# alphanewt_v1_0.net
KiCad netlist of a schematic drawn in EAGLE
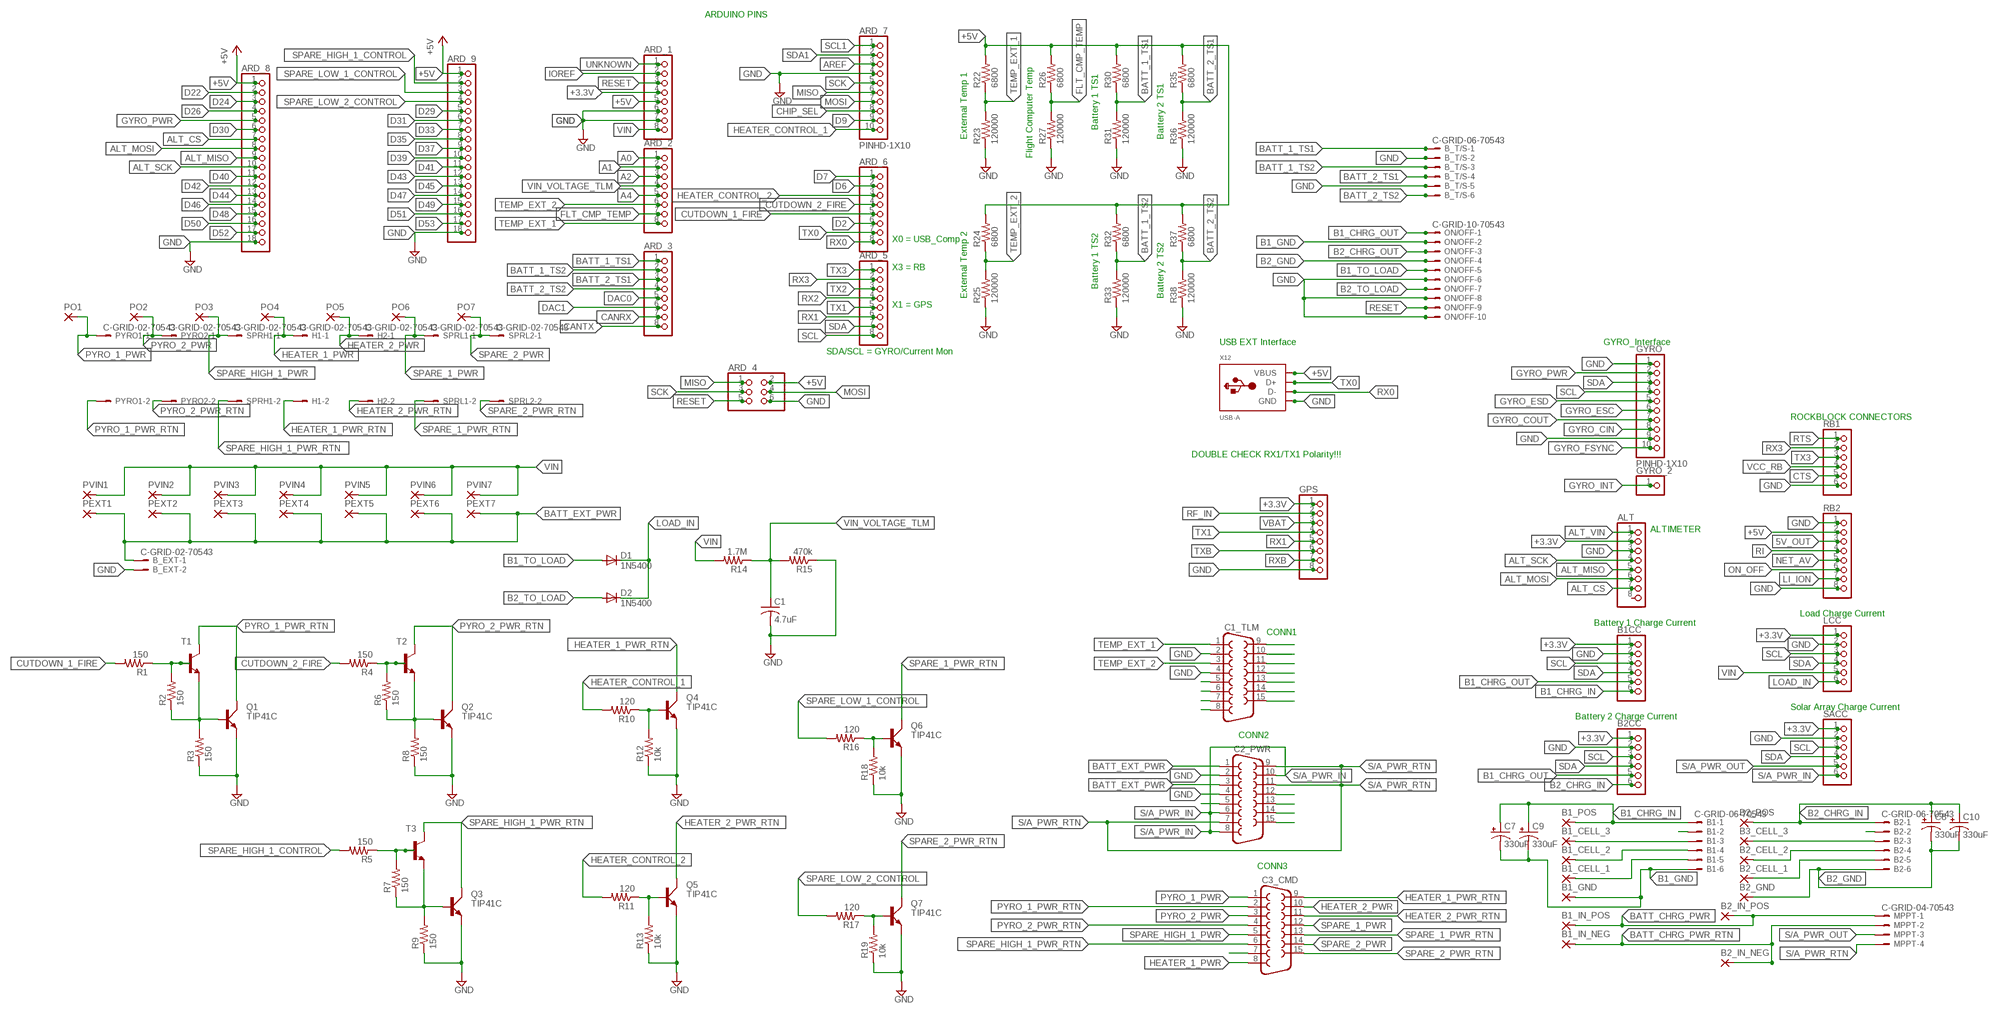
[diagram p0: schematic, sheet 1]

(export (version "E")
  (design (tool "Eeschema 10.0.6"))
  (components
    (comp (ref "ALT")
      (value "PINHD-1X8BIG")
      (footprint "eagle-import:1X08-BIG")
      (libsource (lib "eagle-import") (part "PINHD-1X8BIG"))
    )
    (comp (ref "ARD_1")
      (value "PINHD-1X8BIG")
      (footprint "eagle-import:1X08-BIG")
      (libsource (lib "eagle-import") (part "PINHD-1X8BIG"))
    )
    (comp (ref "ARD_2")
      (value "PINHD-1X8BIG")
      (footprint "eagle-import:1X08-BIG")
      (libsource (lib "eagle-import") (part "PINHD-1X8BIG"))
    )
    (comp (ref "ARD_3")
      (value "PINHD-1X8BIG")
      (footprint "eagle-import:1X08-BIG")
      (libsource (lib "eagle-import") (part "PINHD-1X8BIG"))
    )
    (comp (ref "ARD_4")
      (value "PINHD-2X3")
      (footprint "eagle-import:2X03")
      (libsource (lib "eagle-import") (part "PINHD-2X3"))
    )
    (comp (ref "ARD_5")
      (value "PINHD-1X8BIG")
      (footprint "eagle-import:1X08-BIG")
      (libsource (lib "eagle-import") (part "PINHD-1X8BIG"))
    )
    (comp (ref "ARD_6")
      (value "PINHD-1X8BIG")
      (footprint "eagle-import:1X08-BIG")
      (libsource (lib "eagle-import") (part "PINHD-1X8BIG"))
    )
    (comp (ref "ARD_7")
      (value "PINHD-1X10")
      (footprint "eagle-import:1X10-BIG")
      (libsource (lib "eagle-import") (part "PINHD-1X10"))
    )
    (comp (ref "ARD_8")
      (value "PINHD-1X18-BIG")
      (footprint "eagle-import:1X18-BIG")
      (libsource (lib "eagle-import") (part "PINHD-1X18-BIG"))
    )
    (comp (ref "ARD_9")
      (value "PINHD-1X18-BIG")
      (footprint "eagle-import:1X18-BIG")
      (libsource (lib "eagle-import") (part "PINHD-1X18-BIG"))
    )
    (comp (ref "B1")
      (value "C-GRID-06-70543")
      (footprint "eagle-import:70543-06")
      (fields
        (field (name "MF") "MOLEX")
        (field (name "MPN") "70543-0005")
        (field (name "OC_NEWARK") "59H2647")
      )
      (libsource (lib "eagle-import") (part "C-GRID-06-70543"))
    )
    (comp (ref "B1CC")
      (value "PINHD-1X6B")
      (footprint "eagle-import:1X06-BIG")
      (libsource (lib "eagle-import") (part "PINHD-1X6B"))
    )
    (comp (ref "B1_CELL_1")
      (value "SMD5")
      (footprint "eagle-import:SMD2,54-5,08")
      (libsource (lib "eagle-import") (part "SMD5"))
    )
    (comp (ref "B1_CELL_2")
      (value "SMD5")
      (footprint "eagle-import:SMD2,54-5,08")
      (libsource (lib "eagle-import") (part "SMD5"))
    )
    (comp (ref "B1_CELL_3")
      (value "SMD5")
      (footprint "eagle-import:SMD2,54-5,08")
      (libsource (lib "eagle-import") (part "SMD5"))
    )
    (comp (ref "B1_GND")
      (value "SMD5")
      (footprint "eagle-import:SMD2,54-5,08")
      (libsource (lib "eagle-import") (part "SMD5"))
    )
    (comp (ref "B1_IN_NEG")
      (value "SMD5")
      (footprint "eagle-import:SMD2,54-5,08")
      (libsource (lib "eagle-import") (part "SMD5"))
    )
    (comp (ref "B1_IN_POS")
      (value "SMD5")
      (footprint "eagle-import:SMD2,54-5,08")
      (libsource (lib "eagle-import") (part "SMD5"))
    )
    (comp (ref "B1_POS")
      (value "SMD5")
      (footprint "eagle-import:SMD2,54-5,08")
      (libsource (lib "eagle-import") (part "SMD5"))
    )
    (comp (ref "B2")
      (value "C-GRID-06-70543")
      (footprint "eagle-import:70543-06")
      (fields
        (field (name "MF") "MOLEX")
        (field (name "MPN") "70543-0005")
        (field (name "OC_NEWARK") "59H2647")
      )
      (libsource (lib "eagle-import") (part "C-GRID-06-70543"))
    )
    (comp (ref "B2CC")
      (value "PINHD-1X6B")
      (footprint "eagle-import:1X06-BIG")
      (libsource (lib "eagle-import") (part "PINHD-1X6B"))
    )
    (comp (ref "B2_CELL_1")
      (value "SMD5")
      (footprint "eagle-import:SMD2,54-5,08")
      (libsource (lib "eagle-import") (part "SMD5"))
    )
    (comp (ref "B2_CELL_2")
      (value "SMD5")
      (footprint "eagle-import:SMD2,54-5,08")
      (libsource (lib "eagle-import") (part "SMD5"))
    )
    (comp (ref "B2_GND")
      (value "SMD5")
      (footprint "eagle-import:SMD2,54-5,08")
      (libsource (lib "eagle-import") (part "SMD5"))
    )
    (comp (ref "B2_IN_NEG")
      (value "SMD5")
      (footprint "eagle-import:SMD2,54-5,08")
      (libsource (lib "eagle-import") (part "SMD5"))
    )
    (comp (ref "B2_IN_POS")
      (value "SMD5")
      (footprint "eagle-import:SMD2,54-5,08")
      (libsource (lib "eagle-import") (part "SMD5"))
    )
    (comp (ref "B2_POS")
      (value "SMD5")
      (footprint "eagle-import:SMD2,54-5,08")
      (libsource (lib "eagle-import") (part "SMD5"))
    )
    (comp (ref "B3_CELL_3")
      (value "SMD5")
      (footprint "eagle-import:SMD2,54-5,08")
      (libsource (lib "eagle-import") (part "SMD5"))
    )
    (comp (ref "B_EXT")
      (value "C-GRID-02-70543")
      (footprint "eagle-import:70543-02")
      (fields
        (field (name "MF") "MOLEX")
        (field (name "MPN") "70543-0001")
        (field (name "OC_NEWARK") "59H2645")
      )
      (libsource (lib "eagle-import") (part "C-GRID-02-70543"))
    )
    (comp (ref "B_T/S")
      (value "C-GRID-06-70543")
      (footprint "eagle-import:70543-06")
      (fields
        (field (name "MF") "MOLEX")
        (field (name "MPN") "70543-0005")
        (field (name "OC_NEWARK") "59H2647")
      )
      (libsource (lib "eagle-import") (part "C-GRID-06-70543"))
    )
    (comp (ref "C1")
      (value "4.7uF")
      (footprint "eagle-import:C0805K")
      (fields (field (name "MPN") "C2012X6S1H475K125AC"))
      (libsource (lib "eagle-import") (part "C-USC0805K"))
    )
    (comp (ref "C1_TLM")
      (value "F15HP")
      (footprint "eagle-import:F15HP")
      (fields (field (name "MPN") "5504F1-15S-02A-03"))
      (libsource (lib "eagle-import") (part "F15HP"))
    )
    (comp (ref "C2_PWR")
      (value "F15HP")
      (footprint "eagle-import:F15HP")
      (fields (field (name "MPN") "5504F1-15S-02A-03"))
      (libsource (lib "eagle-import") (part "F15HP"))
    )
    (comp (ref "C3_CMD")
      (value "F15HP")
      (footprint "eagle-import:F15HP")
      (fields (field (name "MPN") "5504F1-15S-02A-03"))
      (libsource (lib "eagle-import") (part "F15HP"))
    )
    (comp (ref "C7")
      (value "330uF")
      (footprint "eagle-import:CT7343")
      (fields (field (name "MPN") "TCN4337M020R0100"))
      (libsource (lib "eagle-import") (part "CPOL-USCT7343"))
    )
    (comp (ref "C8")
      (value "330uF")
      (footprint "eagle-import:CT7343")
      (fields (field (name "MPN") "TCN4337M020R0100"))
      (libsource (lib "eagle-import") (part "CPOL-USCT7343"))
    )
    (comp (ref "C9")
      (value "330uF")
      (footprint "eagle-import:CT7343")
      (fields (field (name "MPN") "TCN4337M020R0100"))
      (libsource (lib "eagle-import") (part "CPOL-USCT7343"))
    )
    (comp (ref "C10")
      (value "330uF")
      (footprint "eagle-import:CT7343")
      (fields (field (name "MPN") "TCN4337M020R0100"))
      (libsource (lib "eagle-import") (part "CPOL-USCT7343"))
    )
    (comp (ref "D1")
      (value "1N5400")
      (footprint "eagle-import:DO201-15")
      (fields (field (name "MPN") "1N5400-E3/54"))
      (libsource (lib "eagle-import") (part "1N5400"))
    )
    (comp (ref "D2")
      (value "1N5400")
      (footprint "eagle-import:DO201-15")
      (fields (field (name "MPN") "1N5400-E3/54"))
      (libsource (lib "eagle-import") (part "1N5400"))
    )
    (comp (ref "GPS")
      (value "PINHD-1X8BIG")
      (footprint "eagle-import:1X08-BIG")
      (libsource (lib "eagle-import") (part "PINHD-1X8BIG"))
    )
    (comp (ref "GYRO")
      (value "PINHD-1X10")
      (footprint "eagle-import:1X10-BIG")
      (libsource (lib "eagle-import") (part "PINHD-1X10"))
    )
    (comp (ref "GYRO_2")
      (value "PINHD-1X1")
      (footprint "eagle-import:1X01")
      (libsource (lib "eagle-import") (part "PINHD-1X1"))
    )
    (comp (ref "H1")
      (value "C-GRID-02-70543")
      (footprint "eagle-import:70543-02")
      (fields
        (field (name "MF") "MOLEX")
        (field (name "MPN") "70543-0001")
        (field (name "OC_NEWARK") "59H2645")
      )
      (libsource (lib "eagle-import") (part "C-GRID-02-70543"))
    )
    (comp (ref "H2")
      (value "C-GRID-02-70543")
      (footprint "eagle-import:70543-02")
      (fields
        (field (name "MF") "MOLEX")
        (field (name "MPN") "70543-0001")
        (field (name "OC_NEWARK") "59H2645")
      )
      (libsource (lib "eagle-import") (part "C-GRID-02-70543"))
    )
    (comp (ref "LCC")
      (value "PINHD-1X6B")
      (footprint "eagle-import:1X06-BIG")
      (libsource (lib "eagle-import") (part "PINHD-1X6B"))
    )
    (comp (ref "MPPT")
      (value "C-GRID-04-70543")
      (footprint "eagle-import:70543-04")
      (fields
        (field (name "MF") "MOLEX")
        (field (name "MPN") "70543-0038")
        (field (name "OC_NEWARK") "59H2665")
      )
      (libsource (lib "eagle-import") (part "C-GRID-04-70543"))
    )
    (comp (ref "ON/OFF")
      (value "C-GRID-10-70543")
      (footprint "eagle-import:70543-10")
      (fields
        (field (name "MF") "MOLEX")
        (field (name "MPN") "70543-0009")
        (field (name "OC_NEWARK") "59H2651")
      )
      (libsource (lib "eagle-import") (part "C-GRID-10-70543"))
    )
    (comp (ref "PEXT1")
      (value "SMD2")
      (footprint "eagle-import:SMD1,27-2,54")
      (libsource (lib "eagle-import") (part "SMD2"))
    )
    (comp (ref "PEXT2")
      (value "SMD2")
      (footprint "eagle-import:SMD1,27-2,54")
      (libsource (lib "eagle-import") (part "SMD2"))
    )
    (comp (ref "PEXT3")
      (value "SMD2")
      (footprint "eagle-import:SMD1,27-2,54")
      (libsource (lib "eagle-import") (part "SMD2"))
    )
    (comp (ref "PEXT4")
      (value "SMD2")
      (footprint "eagle-import:SMD1,27-2,54")
      (libsource (lib "eagle-import") (part "SMD2"))
    )
    (comp (ref "PEXT5")
      (value "SMD2")
      (footprint "eagle-import:SMD1,27-2,54")
      (libsource (lib "eagle-import") (part "SMD2"))
    )
    (comp (ref "PEXT6")
      (value "SMD2")
      (footprint "eagle-import:SMD1,27-2,54")
      (libsource (lib "eagle-import") (part "SMD2"))
    )
    (comp (ref "PEXT7")
      (value "SMD2")
      (footprint "eagle-import:SMD1,27-2,54")
      (libsource (lib "eagle-import") (part "SMD2"))
    )
    (comp (ref "PO1")
      (value "SMD2")
      (footprint "eagle-import:SMD1,27-2,54")
      (libsource (lib "eagle-import") (part "SMD2"))
    )
    (comp (ref "PO2")
      (value "SMD2")
      (footprint "eagle-import:SMD1,27-2,54")
      (libsource (lib "eagle-import") (part "SMD2"))
    )
    (comp (ref "PO3")
      (value "SMD2")
      (footprint "eagle-import:SMD1,27-2,54")
      (libsource (lib "eagle-import") (part "SMD2"))
    )
    (comp (ref "PO4")
      (value "SMD2")
      (footprint "eagle-import:SMD1,27-2,54")
      (libsource (lib "eagle-import") (part "SMD2"))
    )
    (comp (ref "PO5")
      (value "SMD2")
      (footprint "eagle-import:SMD1,27-2,54")
      (libsource (lib "eagle-import") (part "SMD2"))
    )
    (comp (ref "PO6")
      (value "SMD2")
      (footprint "eagle-import:SMD1,27-2,54")
      (libsource (lib "eagle-import") (part "SMD2"))
    )
    (comp (ref "PO7")
      (value "SMD2")
      (footprint "eagle-import:SMD1,27-2,54")
      (libsource (lib "eagle-import") (part "SMD2"))
    )
    (comp (ref "PVIN1")
      (value "SMD2")
      (footprint "eagle-import:SMD1,27-2,54")
      (libsource (lib "eagle-import") (part "SMD2"))
    )
    (comp (ref "PVIN2")
      (value "SMD2")
      (footprint "eagle-import:SMD1,27-2,54")
      (libsource (lib "eagle-import") (part "SMD2"))
    )
    (comp (ref "PVIN3")
      (value "SMD2")
      (footprint "eagle-import:SMD1,27-2,54")
      (libsource (lib "eagle-import") (part "SMD2"))
    )
    (comp (ref "PVIN4")
      (value "SMD2")
      (footprint "eagle-import:SMD1,27-2,54")
      (libsource (lib "eagle-import") (part "SMD2"))
    )
    (comp (ref "PVIN5")
      (value "SMD2")
      (footprint "eagle-import:SMD1,27-2,54")
      (libsource (lib "eagle-import") (part "SMD2"))
    )
    (comp (ref "PVIN6")
      (value "SMD2")
      (footprint "eagle-import:SMD1,27-2,54")
      (libsource (lib "eagle-import") (part "SMD2"))
    )
    (comp (ref "PVIN7")
      (value "SMD2")
      (footprint "eagle-import:SMD1,27-2,54")
      (libsource (lib "eagle-import") (part "SMD2"))
    )
    (comp (ref "PYRO1")
      (value "C-GRID-02-70543")
      (footprint "eagle-import:70543-02")
      (fields
        (field (name "MF") "MOLEX")
        (field (name "MPN") "70543-0001")
        (field (name "OC_NEWARK") "59H2645")
      )
      (libsource (lib "eagle-import") (part "C-GRID-02-70543"))
    )
    (comp (ref "PYRO2")
      (value "C-GRID-02-70543")
      (footprint "eagle-import:70543-02")
      (fields
        (field (name "MF") "MOLEX")
        (field (name "MPN") "70543-0001")
        (field (name "OC_NEWARK") "59H2645")
      )
      (libsource (lib "eagle-import") (part "C-GRID-02-70543"))
    )
    (comp (ref "Q1")
      (value "TIP41C")
      (footprint "eagle-import:TO220AV")
      (fields (field (name "MF") "FAIRCHILD SEMICONDUCTOR"))
      (libsource (lib "eagle-import") (part "TIP41C"))
    )
    (comp (ref "Q2")
      (value "TIP41C")
      (footprint "eagle-import:TO220AV")
      (fields (field (name "MF") "FAIRCHILD SEMICONDUCTOR"))
      (libsource (lib "eagle-import") (part "TIP41C"))
    )
    (comp (ref "Q3")
      (value "TIP41C")
      (footprint "eagle-import:TO220AV")
      (fields (field (name "MF") "FAIRCHILD SEMICONDUCTOR"))
      (libsource (lib "eagle-import") (part "TIP41C"))
    )
    (comp (ref "Q4")
      (value "TIP41C")
      (footprint "eagle-import:TO220AV")
      (fields (field (name "MF") "FAIRCHILD SEMICONDUCTOR"))
      (libsource (lib "eagle-import") (part "TIP41C"))
    )
    (comp (ref "Q5")
      (value "TIP41C")
      (footprint "eagle-import:TO220AV")
      (fields (field (name "MF") "FAIRCHILD SEMICONDUCTOR"))
      (libsource (lib "eagle-import") (part "TIP41C"))
    )
    (comp (ref "Q6")
      (value "TIP41C")
      (footprint "eagle-import:TO220AV")
      (fields (field (name "MF") "FAIRCHILD SEMICONDUCTOR"))
      (libsource (lib "eagle-import") (part "TIP41C"))
    )
    (comp (ref "Q7")
      (value "TIP41C")
      (footprint "eagle-import:TO220AV")
      (fields (field (name "MF") "FAIRCHILD SEMICONDUCTOR"))
      (libsource (lib "eagle-import") (part "TIP41C"))
    )
    (comp (ref "R1")
      (value "150")
      (footprint "eagle-import:R0805")
      (fields (field (name "MF") "VISHAY/DALE") (field (name "MPN") "CRCW120633R2FKEA"))
      (libsource (lib "eagle-import") (part "R-US_R0805"))
    )
    (comp (ref "R2")
      (value "150")
      (footprint "eagle-import:R0805")
      (fields (field (name "MF") "VISHAY/DALE") (field (name "MPN") "CRCW120633R2FKEA"))
      (libsource (lib "eagle-import") (part "R-US_R0805"))
    )
    (comp (ref "R3")
      (value "150")
      (footprint "eagle-import:R0805")
      (fields (field (name "MF") "VISHAY/DALE") (field (name "MPN") "CRCW120633R2FKEA"))
      (libsource (lib "eagle-import") (part "R-US_R0805"))
    )
    (comp (ref "R4")
      (value "150")
      (footprint "eagle-import:R0805")
      (fields (field (name "MF") "VISHAY/DALE") (field (name "MPN") "CRCW120633R2FKEA"))
      (libsource (lib "eagle-import") (part "R-US_R0805"))
    )
    (comp (ref "R5")
      (value "150")
      (footprint "eagle-import:R0805")
      (fields (field (name "MF") "VISHAY/DALE") (field (name "MPN") "CRCW120633R2FKEA"))
      (libsource (lib "eagle-import") (part "R-US_R0805"))
    )
    (comp (ref "R6")
      (value "150")
      (footprint "eagle-import:R0805")
      (fields (field (name "MF") "VISHAY/DALE") (field (name "MPN") "CRCW120633R2FKEA"))
      (libsource (lib "eagle-import") (part "R-US_R0805"))
    )
    (comp (ref "R7")
      (value "150")
      (footprint "eagle-import:R0805")
      (fields (field (name "MF") "VISHAY/DALE") (field (name "MPN") "CRCW120633R2FKEA"))
      (libsource (lib "eagle-import") (part "R-US_R0805"))
    )
    (comp (ref "R8")
      (value "150")
      (footprint "eagle-import:R0805")
      (fields (field (name "MF") "VISHAY/DALE") (field (name "MPN") "CRCW120633R2FKEA"))
      (libsource (lib "eagle-import") (part "R-US_R0805"))
    )
    (comp (ref "R9")
      (value "150")
      (footprint "eagle-import:R0805")
      (fields (field (name "MF") "VISHAY/DALE") (field (name "MPN") "CRCW120633R2FKEA"))
      (libsource (lib "eagle-import") (part "R-US_R0805"))
    )
    (comp (ref "R10")
      (value "120")
      (footprint "eagle-import:R0805")
      (fields (field (name "MF") "VISHAY/DALE") (field (name "MPN") "CRCW120633R2FKEA"))
      (libsource (lib "eagle-import") (part "R-US_R0805"))
    )
    (comp (ref "R11")
      (value "120")
      (footprint "eagle-import:R0805")
      (fields (field (name "MF") "VISHAY/DALE") (field (name "MPN") "CRCW120633R2FKEA"))
      (libsource (lib "eagle-import") (part "R-US_R0805"))
    )
    (comp (ref "R12")
      (value "10k")
      (footprint "eagle-import:R0805")
      (fields (field (name "MF") "VISHAY/DALE") (field (name "MPN") "CRCW120633R2FKEA"))
      (libsource (lib "eagle-import") (part "R-US_R0805"))
    )
    (comp (ref "R13")
      (value "10k")
      (footprint "eagle-import:R0805")
      (fields (field (name "MF") "VISHAY/DALE") (field (name "MPN") "CRCW120633R2FKEA"))
      (libsource (lib "eagle-import") (part "R-US_R0805"))
    )
    (comp (ref "R14")
      (value "1.7M")
      (footprint "eagle-import:R0805")
      (fields (field (name "MF") "VISHAY/DALE") (field (name "MPN") "CRCW120633R2FKEA"))
      (libsource (lib "eagle-import") (part "R-US_R0805"))
    )
    (comp (ref "R15")
      (value "470k")
      (footprint "eagle-import:R0805")
      (fields (field (name "MF") "VISHAY/DALE") (field (name "MPN") "CRCW120633R2FKEA"))
      (libsource (lib "eagle-import") (part "R-US_R0805"))
    )
    (comp (ref "R16")
      (value "120")
      (footprint "eagle-import:R0805")
      (fields (field (name "MF") "VISHAY/DALE") (field (name "MPN") "CRCW120633R2FKEA"))
      (libsource (lib "eagle-import") (part "R-US_R0805"))
    )
    (comp (ref "R17")
      (value "120")
      (footprint "eagle-import:R0805")
      (fields (field (name "MF") "VISHAY/DALE") (field (name "MPN") "CRCW120633R2FKEA"))
      (libsource (lib "eagle-import") (part "R-US_R0805"))
    )
    (comp (ref "R18")
      (value "10k")
      (footprint "eagle-import:R0805")
      (fields (field (name "MF") "VISHAY/DALE") (field (name "MPN") "CRCW120633R2FKEA"))
      (libsource (lib "eagle-import") (part "R-US_R0805"))
    )
    (comp (ref "R19")
      (value "10k")
      (footprint "eagle-import:R0805")
      (fields (field (name "MF") "VISHAY/DALE") (field (name "MPN") "CRCW120633R2FKEA"))
      (libsource (lib "eagle-import") (part "R-US_R0805"))
    )
    (comp (ref "R22")
      (value "6800")
      (footprint "eagle-import:R0805")
      (fields (field (name "MF") "VISHAY/DALE") (field (name "MPN") "CRCW120633R2FKEA"))
      (libsource (lib "eagle-import") (part "R-US_R0805"))
    )
    (comp (ref "R23")
      (value "120000")
      (footprint "eagle-import:R0805")
      (fields (field (name "MF") "VISHAY/DALE") (field (name "MPN") "CRCW120633R2FKEA"))
      (libsource (lib "eagle-import") (part "R-US_R0805"))
    )
    (comp (ref "R24")
      (value "6800")
      (footprint "eagle-import:R0805")
      (fields (field (name "MF") "VISHAY/DALE") (field (name "MPN") "CRCW120633R2FKEA"))
      (libsource (lib "eagle-import") (part "R-US_R0805"))
    )
    (comp (ref "R25")
      (value "120000")
      (footprint "eagle-import:R0805")
      (fields (field (name "MF") "VISHAY/DALE") (field (name "MPN") "CRCW120633R2FKEA"))
      (libsource (lib "eagle-import") (part "R-US_R0805"))
    )
    (comp (ref "R26")
      (value "6800")
      (footprint "eagle-import:R0805")
      (fields (field (name "MF") "VISHAY/DALE") (field (name "MPN") "CRCW120633R2FKEA"))
      (libsource (lib "eagle-import") (part "R-US_R0805"))
    )
    (comp (ref "R27")
      (value "120000")
      (footprint "eagle-import:R0805")
      (fields (field (name "MF") "VISHAY/DALE") (field (name "MPN") "CRCW120633R2FKEA"))
      (libsource (lib "eagle-import") (part "R-US_R0805"))
    )
    (comp (ref "R30")
      (value "6800")
      (footprint "eagle-import:R0805")
      (fields (field (name "MF") "VISHAY/DALE") (field (name "MPN") "CRCW120633R2FKEA"))
      (libsource (lib "eagle-import") (part "R-US_R0805"))
    )
    (comp (ref "R31")
      (value "120000")
      (footprint "eagle-import:R0805")
      (fields (field (name "MF") "VISHAY/DALE") (field (name "MPN") "CRCW120633R2FKEA"))
      (libsource (lib "eagle-import") (part "R-US_R0805"))
    )
    (comp (ref "R32")
      (value "6800")
      (footprint "eagle-import:R0805")
      (fields (field (name "MF") "VISHAY/DALE") (field (name "MPN") "CRCW120633R2FKEA"))
      (libsource (lib "eagle-import") (part "R-US_R0805"))
    )
    (comp (ref "R33")
      (value "120000")
      (footprint "eagle-import:R0805")
      (fields (field (name "MF") "VISHAY/DALE") (field (name "MPN") "CRCW120633R2FKEA"))
      (libsource (lib "eagle-import") (part "R-US_R0805"))
    )
    (comp (ref "R35")
      (value "6800")
      (footprint "eagle-import:R0805")
      (fields (field (name "MF") "VISHAY/DALE") (field (name "MPN") "CRCW120633R2FKEA"))
      (libsource (lib "eagle-import") (part "R-US_R0805"))
    )
    (comp (ref "R36")
      (value "120000")
      (footprint "eagle-import:R0805")
      (fields (field (name "MF") "VISHAY/DALE") (field (name "MPN") "CRCW120633R2FKEA"))
      (libsource (lib "eagle-import") (part "R-US_R0805"))
    )
    (comp (ref "R37")
      (value "6800")
      (footprint "eagle-import:R0805")
      (fields (field (name "MF") "VISHAY/DALE") (field (name "MPN") "CRCW120633R2FKEA"))
      (libsource (lib "eagle-import") (part "R-US_R0805"))
    )
    (comp (ref "R38")
      (value "120000")
      (footprint "eagle-import:R0805")
      (fields (field (name "MF") "VISHAY/DALE") (field (name "MPN") "CRCW120633R2FKEA"))
      (libsource (lib "eagle-import") (part "R-US_R0805"))
    )
    (comp (ref "RB1")
      (value "PINHD-1X6CB")
      (footprint "eagle-import:1X06-CLEANBIG")
      (libsource (lib "eagle-import") (part "PINHD-1X6CB"))
    )
    (comp (ref "RB2")
      (value "PINHD-1X8BIG")
      (footprint "eagle-import:1X08-BIG")
      (libsource (lib "eagle-import") (part "PINHD-1X8BIG"))
    )
    (comp (ref "SACC")
      (value "PINHD-1X6B")
      (footprint "eagle-import:1X06-BIG")
      (libsource (lib "eagle-import") (part "PINHD-1X6B"))
    )
    (comp (ref "SPRH1")
      (value "C-GRID-02-70543")
      (footprint "eagle-import:70543-02")
      (fields
        (field (name "MF") "MOLEX")
        (field (name "MPN") "70543-0001")
        (field (name "OC_NEWARK") "59H2645")
      )
      (libsource (lib "eagle-import") (part "C-GRID-02-70543"))
    )
    (comp (ref "SPRL1")
      (value "C-GRID-02-70543")
      (footprint "eagle-import:70543-02")
      (fields
        (field (name "MF") "MOLEX")
        (field (name "MPN") "70543-0001")
        (field (name "OC_NEWARK") "59H2645")
      )
      (libsource (lib "eagle-import") (part "C-GRID-02-70543"))
    )
    (comp (ref "SPRL2")
      (value "C-GRID-02-70543")
      (footprint "eagle-import:70543-02")
      (fields
        (field (name "MF") "MOLEX")
        (field (name "MPN") "70543-0001")
        (field (name "OC_NEWARK") "59H2645")
      )
      (libsource (lib "eagle-import") (part "C-GRID-02-70543"))
    )
    (comp (ref "T1")
      (value "2N3904")
      (footprint "eagle-import:TO92")
      (fields (field (name "MF") "NTE ELECTRONICS"))
      (libsource (lib "eagle-import") (part "2N3904"))
    )
    (comp (ref "T2")
      (value "2N3904")
      (footprint "eagle-import:TO92")
      (fields (field (name "MF") "NTE ELECTRONICS"))
      (libsource (lib "eagle-import") (part "2N3904"))
    )
    (comp (ref "T3")
      (value "2N3904")
      (footprint "eagle-import:TO92")
      (fields (field (name "MF") "NTE ELECTRONICS"))
      (libsource (lib "eagle-import") (part "2N3904"))
    )
    (comp (ref "X12")
      (value "USB-A")
      (footprint "eagle-import:MOLEX_480371000")
      (fields (field (name "MPN") "UE27-AC54-10H"))
      (libsource (lib "eagle-import") (part "USB-A"))
    )
  )
  (nets
    (net (code "1") (name "+3.3V") (class "Default")
      (node (ref "ALT") (pin "2") (pinfunction "2_2") (pintype "passive"))
      (node (ref "ARD_1") (pin "4") (pinfunction "4_4") (pintype "passive"))
      (node (ref "B1CC") (pin "1") (pinfunction "1_1") (pintype "passive"))
      (node (ref "B2CC") (pin "1") (pinfunction "1_1") (pintype "passive"))
      (node (ref "GPS") (pin "1") (pinfunction "1_1") (pintype "passive"))
      (node (ref "LCC") (pin "1") (pinfunction "1_1") (pintype "passive"))
      (node (ref "SACC") (pin "1") (pinfunction "1_1") (pintype "passive"))
    )
    (net (code "2") (name "+5V") (class "Default")
      (node (ref "ARD_1") (pin "5") (pinfunction "5_5") (pintype "passive"))
      (node (ref "ARD_4") (pin "2") (pinfunction "2_2") (pintype "passive"))
      (node (ref "ARD_8") (pin "1") (pinfunction "1_1") (pintype "passive"))
      (node (ref "ARD_9") (pin "1") (pinfunction "1_1") (pintype "passive"))
      (node (ref "R22") (pin "2") (pinfunction "2_2") (pintype "passive"))
      (node (ref "R24") (pin "2") (pinfunction "2_2") (pintype "passive"))
      (node (ref "R26") (pin "2") (pinfunction "2_2") (pintype "passive"))
      (node (ref "R30") (pin "2") (pinfunction "2_2") (pintype "passive"))
      (node (ref "R32") (pin "2") (pinfunction "2_2") (pintype "passive"))
      (node (ref "R35") (pin "2") (pinfunction "2_2") (pintype "passive"))
      (node (ref "R37") (pin "2") (pinfunction "2_2") (pintype "passive"))
      (node (ref "RB2") (pin "2") (pinfunction "2_2") (pintype "passive"))
      (node (ref "X12") (pin "1") (pinfunction "VBUS_1") (pintype "power_in"))
    )
    (net (code "3") (name "5V_OUT") (class "Default")
      (node (ref "RB2") (pin "3") (pinfunction "3_3") (pintype "passive"))
    )
    (net (code "4") (name "A0") (class "Default")
      (node (ref "ARD_2") (pin "1") (pinfunction "1_1") (pintype "passive"))
    )
    (net (code "5") (name "A1") (class "Default")
      (node (ref "ARD_2") (pin "2") (pinfunction "2_2") (pintype "passive"))
    )
    (net (code "6") (name "A2") (class "Default")
      (node (ref "ARD_2") (pin "3") (pinfunction "3_3") (pintype "passive"))
    )
    (net (code "7") (name "A4") (class "Default")
      (node (ref "ARD_2") (pin "5") (pinfunction "5_5") (pintype "passive"))
    )
    (net (code "8") (name "ALT_CS") (class "Default")
      (node (ref "ALT") (pin "7") (pinfunction "7_7") (pintype "passive"))
      (node (ref "ARD_8") (pin "7") (pinfunction "7_7") (pintype "passive"))
    )
    (net (code "9") (name "ALT_MISO") (class "Default")
      (node (ref "ALT") (pin "5") (pinfunction "5_5") (pintype "passive"))
      (node (ref "ARD_8") (pin "9") (pinfunction "9_9") (pintype "passive"))
    )
    (net (code "10") (name "ALT_MOSI") (class "Default")
      (node (ref "ALT") (pin "6") (pinfunction "6_6") (pintype "passive"))
      (node (ref "ARD_8") (pin "8") (pinfunction "8_8") (pintype "passive"))
    )
    (net (code "11") (name "ALT_SCK") (class "Default")
      (node (ref "ALT") (pin "4") (pinfunction "4_4") (pintype "passive"))
      (node (ref "ARD_8") (pin "10") (pinfunction "10_10") (pintype "passive"))
    )
    (net (code "12") (name "ALT_VIN") (class "Default")
      (node (ref "ALT") (pin "1") (pinfunction "1_1") (pintype "passive"))
    )
    (net (code "13") (name "AREF") (class "Default")
      (node (ref "ARD_7") (pin "3") (pinfunction "3_3") (pintype "passive"))
    )
    (net (code "14") (name "B1_CHRG_IN") (class "Default")
      (node (ref "B1") (pin "1") (pinfunction "S_1") (pintype "passive"))
      (node (ref "B1CC") (pin "6") (pinfunction "6_6") (pintype "passive"))
      (node (ref "B1_POS") (pin "1") (pinfunction "P_1") (pintype "passive"))
      (node (ref "C7") (pin "+") (pinfunction "+_+") (pintype "passive"))
      (node (ref "C9") (pin "+") (pinfunction "+_+") (pintype "passive"))
    )
    (net (code "15") (name "B1_CHRG_OUT") (class "Default")
      (node (ref "B1CC") (pin "5") (pinfunction "5_5") (pintype "passive"))
      (node (ref "B2CC") (pin "5") (pinfunction "5_5") (pintype "passive"))
      (node (ref "ON/OFF") (pin "1") (pinfunction "S_1") (pintype "passive"))
    )
    (net (code "16") (name "B1_GND") (class "Default")
      (node (ref "B1") (pin "6") (pinfunction "S_6") (pintype "passive"))
      (node (ref "B1_GND") (pin "1") (pinfunction "P_1") (pintype "passive"))
      (node (ref "C7") (pin "-") (pinfunction "-_-") (pintype "passive"))
      (node (ref "C9") (pin "-") (pinfunction "-_-") (pintype "passive"))
      (node (ref "ON/OFF") (pin "2") (pinfunction "S_2") (pintype "passive"))
    )
    (net (code "17") (name "B1_TO_LOAD") (class "Default")
      (node (ref "D1") (pin "A") (pinfunction "A_A") (pintype "passive"))
      (node (ref "ON/OFF") (pin "5") (pinfunction "S_5") (pintype "passive"))
    )
    (net (code "18") (name "B2_CHRG_IN") (class "Default")
      (node (ref "B2") (pin "1") (pinfunction "S_1") (pintype "passive"))
      (node (ref "B2CC") (pin "6") (pinfunction "6_6") (pintype "passive"))
      (node (ref "B2_POS") (pin "1") (pinfunction "P_1") (pintype "passive"))
      (node (ref "C10") (pin "+") (pinfunction "+_+") (pintype "passive"))
      (node (ref "C8") (pin "+") (pinfunction "+_+") (pintype "passive"))
    )
    (net (code "19") (name "B2_CHRG_OUT") (class "Default")
      (node (ref "ON/OFF") (pin "3") (pinfunction "S_3") (pintype "passive"))
    )
    (net (code "20") (name "B2_GND") (class "Default")
      (node (ref "B2") (pin "6") (pinfunction "S_6") (pintype "passive"))
      (node (ref "B2_GND") (pin "1") (pinfunction "P_1") (pintype "passive"))
      (node (ref "C10") (pin "-") (pinfunction "-_-") (pintype "passive"))
      (node (ref "C8") (pin "-") (pinfunction "-_-") (pintype "passive"))
      (node (ref "ON/OFF") (pin "4") (pinfunction "S_4") (pintype "passive"))
    )
    (net (code "21") (name "B2_TO_LOAD") (class "Default")
      (node (ref "D2") (pin "A") (pinfunction "A_A") (pintype "passive"))
      (node (ref "ON/OFF") (pin "7") (pinfunction "S_7") (pintype "passive"))
    )
    (net (code "22") (name "BATT_1_TS1") (class "Default")
      (node (ref "ARD_3") (pin "1") (pinfunction "1_1") (pintype "passive"))
      (node (ref "B_T/S") (pin "1") (pinfunction "S_1") (pintype "passive"))
      (node (ref "R30") (pin "1") (pinfunction "1_1") (pintype "passive"))
      (node (ref "R31") (pin "2") (pinfunction "2_2") (pintype "passive"))
    )
    (net (code "23") (name "BATT_1_TS2") (class "Default")
      (node (ref "ARD_3") (pin "2") (pinfunction "2_2") (pintype "passive"))
      (node (ref "B_T/S") (pin "3") (pinfunction "S_3") (pintype "passive"))
      (node (ref "R32") (pin "1") (pinfunction "1_1") (pintype "passive"))
      (node (ref "R33") (pin "2") (pinfunction "2_2") (pintype "passive"))
    )
    (net (code "24") (name "BATT_2_TS1") (class "Default")
      (node (ref "ARD_3") (pin "3") (pinfunction "3_3") (pintype "passive"))
      (node (ref "B_T/S") (pin "4") (pinfunction "S_4") (pintype "passive"))
      (node (ref "R35") (pin "1") (pinfunction "1_1") (pintype "passive"))
      (node (ref "R36") (pin "2") (pinfunction "2_2") (pintype "passive"))
    )
    (net (code "25") (name "BATT_2_TS2") (class "Default")
      (node (ref "ARD_3") (pin "4") (pinfunction "4_4") (pintype "passive"))
      (node (ref "B_T/S") (pin "6") (pinfunction "S_6") (pintype "passive"))
      (node (ref "R37") (pin "1") (pinfunction "1_1") (pintype "passive"))
      (node (ref "R38") (pin "2") (pinfunction "2_2") (pintype "passive"))
    )
    (net (code "26") (name "BATT_CHRG_PWR") (class "Default")
      (node (ref "B1_IN_POS") (pin "1") (pinfunction "P_1") (pintype "passive"))
      (node (ref "B2_IN_POS") (pin "1") (pinfunction "P_1") (pintype "passive"))
      (node (ref "MPPT") (pin "1") (pinfunction "S_1") (pintype "passive"))
    )
    (net (code "27") (name "BATT_CHRG_PWR_RTN") (class "Default")
      (node (ref "B1_IN_NEG") (pin "1") (pinfunction "P_1") (pintype "passive"))
      (node (ref "B2_IN_NEG") (pin "1") (pinfunction "P_1") (pintype "passive"))
      (node (ref "MPPT") (pin "2") (pinfunction "S_2") (pintype "passive"))
    )
    (net (code "28") (name "BATT_EXT_PWR") (class "Default")
      (node (ref "B_EXT") (pin "1") (pinfunction "S_1") (pintype "passive"))
      (node (ref "C2_PWR") (pin "1") (pinfunction "1_1") (pintype "passive"))
      (node (ref "C2_PWR") (pin "3") (pinfunction "3_3") (pintype "passive"))
      (node (ref "PEXT1") (pin "1") (pinfunction "P_1") (pintype "passive"))
      (node (ref "PEXT2") (pin "1") (pinfunction "P_1") (pintype "passive"))
      (node (ref "PEXT3") (pin "1") (pinfunction "P_1") (pintype "passive"))
      (node (ref "PEXT4") (pin "1") (pinfunction "P_1") (pintype "passive"))
      (node (ref "PEXT5") (pin "1") (pinfunction "P_1") (pintype "passive"))
      (node (ref "PEXT6") (pin "1") (pinfunction "P_1") (pintype "passive"))
      (node (ref "PEXT7") (pin "1") (pinfunction "P_1") (pintype "passive"))
    )
    (net (code "29") (name "CANRX") (class "Default")
      (node (ref "ARD_3") (pin "7") (pinfunction "7_7") (pintype "passive"))
    )
    (net (code "30") (name "CANTX") (class "Default")
      (node (ref "ARD_3") (pin "8") (pinfunction "8_8") (pintype "passive"))
    )
    (net (code "31") (name "CHIP_SEL") (class "Default")
      (node (ref "ARD_7") (pin "8") (pinfunction "8_8") (pintype "passive"))
    )
    (net (code "32") (name "CTS") (class "Default")
      (node (ref "RB1") (pin "5") (pinfunction "5_5") (pintype "passive"))
    )
    (net (code "33") (name "CUTDOWN_1_FIRE") (class "Default")
      (node (ref "ARD_6") (pin "5") (pinfunction "5_5") (pintype "passive"))
      (node (ref "R1") (pin "2") (pinfunction "2_2") (pintype "passive"))
    )
    (net (code "34") (name "CUTDOWN_2_FIRE") (class "Default")
      (node (ref "ARD_6") (pin "4") (pinfunction "4_4") (pintype "passive"))
      (node (ref "R4") (pin "2") (pinfunction "2_2") (pintype "passive"))
    )
    (net (code "35") (name "D2") (class "Default")
      (node (ref "ARD_6") (pin "6") (pinfunction "6_6") (pintype "passive"))
    )
    (net (code "36") (name "D6") (class "Default")
      (node (ref "ARD_6") (pin "2") (pinfunction "2_2") (pintype "passive"))
    )
    (net (code "37") (name "D7") (class "Default")
      (node (ref "ARD_6") (pin "1") (pinfunction "1_1") (pintype "passive"))
    )
    (net (code "38") (name "D9") (class "Default")
      (node (ref "ARD_7") (pin "9") (pinfunction "9_9") (pintype "passive"))
    )
    (net (code "39") (name "D22") (class "Default")
      (node (ref "ARD_8") (pin "2") (pinfunction "2_2") (pintype "passive"))
    )
    (net (code "40") (name "D24") (class "Default")
      (node (ref "ARD_8") (pin "3") (pinfunction "3_3") (pintype "passive"))
    )
    (net (code "41") (name "D26") (class "Default")
      (node (ref "ARD_8") (pin "4") (pinfunction "4_4") (pintype "passive"))
    )
    (net (code "42") (name "D29") (class "Default")
      (node (ref "ARD_9") (pin "5") (pinfunction "5_5") (pintype "passive"))
    )
    (net (code "43") (name "D30") (class "Default")
      (node (ref "ARD_8") (pin "6") (pinfunction "6_6") (pintype "passive"))
    )
    (net (code "44") (name "D31") (class "Default")
      (node (ref "ARD_9") (pin "6") (pinfunction "6_6") (pintype "passive"))
    )
    (net (code "45") (name "D33") (class "Default")
      (node (ref "ARD_9") (pin "7") (pinfunction "7_7") (pintype "passive"))
    )
    (net (code "46") (name "D35") (class "Default")
      (node (ref "ARD_9") (pin "8") (pinfunction "8_8") (pintype "passive"))
    )
    (net (code "47") (name "D37") (class "Default")
      (node (ref "ARD_9") (pin "9") (pinfunction "9_9") (pintype "passive"))
    )
    (net (code "48") (name "D39") (class "Default")
      (node (ref "ARD_9") (pin "10") (pinfunction "10_10") (pintype "passive"))
    )
    (net (code "49") (name "D40") (class "Default")
      (node (ref "ARD_8") (pin "11") (pinfunction "11_11") (pintype "passive"))
    )
    (net (code "50") (name "D41") (class "Default")
      (node (ref "ARD_9") (pin "11") (pinfunction "11_11") (pintype "passive"))
    )
    (net (code "51") (name "D42") (class "Default")
      (node (ref "ARD_8") (pin "12") (pinfunction "12_12") (pintype "passive"))
    )
    (net (code "52") (name "D43") (class "Default")
      (node (ref "ARD_9") (pin "12") (pinfunction "12_12") (pintype "passive"))
    )
    (net (code "53") (name "D44") (class "Default")
      (node (ref "ARD_8") (pin "13") (pinfunction "13_13") (pintype "passive"))
    )
    (net (code "54") (name "D45") (class "Default")
      (node (ref "ARD_9") (pin "13") (pinfunction "13_13") (pintype "passive"))
    )
    (net (code "55") (name "D46") (class "Default")
      (node (ref "ARD_8") (pin "14") (pinfunction "14_14") (pintype "passive"))
    )
    (net (code "56") (name "D47") (class "Default")
      (node (ref "ARD_9") (pin "14") (pinfunction "14_14") (pintype "passive"))
    )
    (net (code "57") (name "D48") (class "Default")
      (node (ref "ARD_8") (pin "15") (pinfunction "15_15") (pintype "passive"))
    )
    (net (code "58") (name "D49") (class "Default")
      (node (ref "ARD_9") (pin "15") (pinfunction "15_15") (pintype "passive"))
    )
    (net (code "59") (name "D50") (class "Default")
      (node (ref "ARD_8") (pin "16") (pinfunction "16_16") (pintype "passive"))
    )
    (net (code "60") (name "D51") (class "Default")
      (node (ref "ARD_9") (pin "16") (pinfunction "16_16") (pintype "passive"))
    )
    (net (code "61") (name "D52") (class "Default")
      (node (ref "ARD_8") (pin "17") (pinfunction "17_17") (pintype "passive"))
    )
    (net (code "62") (name "D53") (class "Default")
      (node (ref "ARD_9") (pin "17") (pinfunction "17_17") (pintype "passive"))
    )
    (net (code "63") (name "DAC0") (class "Default")
      (node (ref "ARD_3") (pin "5") (pinfunction "5_5") (pintype "passive"))
    )
    (net (code "64") (name "DAC1") (class "Default")
      (node (ref "ARD_3") (pin "6") (pinfunction "6_6") (pintype "passive"))
    )
    (net (code "65") (name "FLT_CMP_TEMP") (class "Default")
      (node (ref "ARD_2") (pin "7") (pinfunction "7_7") (pintype "passive"))
      (node (ref "R26") (pin "1") (pinfunction "1_1") (pintype "passive"))
      (node (ref "R27") (pin "2") (pinfunction "2_2") (pintype "passive"))
    )
    (net (code "66") (name "GND") (class "Default")
      (node (ref "ALT") (pin "3") (pinfunction "3_3") (pintype "passive"))
      (node (ref "ARD_1") (pin "6") (pinfunction "6_6") (pintype "passive"))
      (node (ref "ARD_1") (pin "7") (pinfunction "7_7") (pintype "passive"))
      (node (ref "ARD_4") (pin "6") (pinfunction "6_6") (pintype "passive"))
      (node (ref "ARD_7") (pin "4") (pinfunction "4_4") (pintype "passive"))
      (node (ref "ARD_8") (pin "18") (pinfunction "18_18") (pintype "passive"))
      (node (ref "ARD_9") (pin "18") (pinfunction "18_18") (pintype "passive"))
      (node (ref "B1CC") (pin "2") (pinfunction "2_2") (pintype "passive"))
      (node (ref "B2CC") (pin "2") (pinfunction "2_2") (pintype "passive"))
      (node (ref "B_EXT") (pin "2") (pinfunction "S_2") (pintype "passive"))
      (node (ref "B_T/S") (pin "2") (pinfunction "S_2") (pintype "passive"))
      (node (ref "B_T/S") (pin "5") (pinfunction "S_5") (pintype "passive"))
      (node (ref "C1") (pin "2") (pinfunction "2_2") (pintype "passive"))
      (node (ref "C1_TLM") (pin "2") (pinfunction "2_2") (pintype "passive"))
      (node (ref "C1_TLM") (pin "4") (pinfunction "4_4") (pintype "passive"))
      (node (ref "C2_PWR") (pin "2") (pinfunction "2_2") (pintype "passive"))
      (node (ref "C2_PWR") (pin "4") (pinfunction "4_4") (pintype "passive"))
      (node (ref "GPS") (pin "8") (pinfunction "8_8") (pintype "passive"))
      (node (ref "GYRO") (pin "1") (pinfunction "1_1") (pintype "passive"))
      (node (ref "GYRO") (pin "9") (pinfunction "9_9") (pintype "passive"))
      (node (ref "LCC") (pin "2") (pinfunction "2_2") (pintype "passive"))
      (node (ref "ON/OFF") (pin "10") (pinfunction "S_10") (pintype "passive"))
      (node (ref "ON/OFF") (pin "6") (pinfunction "S_6") (pintype "passive"))
      (node (ref "ON/OFF") (pin "8") (pinfunction "S_8") (pintype "passive"))
      (node (ref "Q1") (pin "E") (pinfunction "E_E") (pintype "passive"))
      (node (ref "Q2") (pin "E") (pinfunction "E_E") (pintype "passive"))
      (node (ref "Q3") (pin "E") (pinfunction "E_E") (pintype "passive"))
      (node (ref "Q4") (pin "E") (pinfunction "E_E") (pintype "passive"))
      (node (ref "Q5") (pin "E") (pinfunction "E_E") (pintype "passive"))
      (node (ref "Q6") (pin "E") (pinfunction "E_E") (pintype "passive"))
      (node (ref "Q7") (pin "E") (pinfunction "E_E") (pintype "passive"))
      (node (ref "R12") (pin "1") (pinfunction "1_1") (pintype "passive"))
      (node (ref "R13") (pin "1") (pinfunction "1_1") (pintype "passive"))
      (node (ref "R15") (pin "1") (pinfunction "1_1") (pintype "passive"))
      (node (ref "R18") (pin "1") (pinfunction "1_1") (pintype "passive"))
      (node (ref "R19") (pin "1") (pinfunction "1_1") (pintype "passive"))
      (node (ref "R23") (pin "1") (pinfunction "1_1") (pintype "passive"))
      (node (ref "R25") (pin "1") (pinfunction "1_1") (pintype "passive"))
      (node (ref "R27") (pin "1") (pinfunction "1_1") (pintype "passive"))
      (node (ref "R3") (pin "1") (pinfunction "1_1") (pintype "passive"))
      (node (ref "R31") (pin "1") (pinfunction "1_1") (pintype "passive"))
      (node (ref "R33") (pin "1") (pinfunction "1_1") (pintype "passive"))
      (node (ref "R36") (pin "1") (pinfunction "1_1") (pintype "passive"))
      (node (ref "R38") (pin "1") (pinfunction "1_1") (pintype "passive"))
      (node (ref "R8") (pin "1") (pinfunction "1_1") (pintype "passive"))
      (node (ref "R9") (pin "1") (pinfunction "1_1") (pintype "passive"))
      (node (ref "RB1") (pin "6") (pinfunction "6_6") (pintype "passive"))
      (node (ref "RB2") (pin "1") (pinfunction "1_1") (pintype "passive"))
      (node (ref "RB2") (pin "8") (pinfunction "8_8") (pintype "passive"))
      (node (ref "SACC") (pin "2") (pinfunction "2_2") (pintype "passive"))
      (node (ref "X12") (pin "4") (pinfunction "GND_4") (pintype "power_in"))
    )
    (net (code "67") (name "GYRO_CIN") (class "Default")
      (node (ref "GYRO") (pin "8") (pinfunction "8_8") (pintype "passive"))
    )
    (net (code "68") (name "GYRO_COUT") (class "Default")
      (node (ref "GYRO") (pin "7") (pinfunction "7_7") (pintype "passive"))
    )
    (net (code "69") (name "GYRO_ESC") (class "Default")
      (node (ref "GYRO") (pin "6") (pinfunction "6_6") (pintype "passive"))
    )
    (net (code "70") (name "GYRO_ESD") (class "Default")
      (node (ref "GYRO") (pin "5") (pinfunction "5_5") (pintype "passive"))
    )
    (net (code "71") (name "GYRO_FSYNC") (class "Default")
      (node (ref "GYRO") (pin "10") (pinfunction "10_10") (pintype "passive"))
    )
    (net (code "72") (name "GYRO_INT") (class "Default")
      (node (ref "GYRO_2") (pin "1") (pinfunction "1_1") (pintype "passive"))
    )
    (net (code "73") (name "GYRO_PWR") (class "Default")
      (node (ref "ARD_8") (pin "5") (pinfunction "5_5") (pintype "passive"))
      (node (ref "GYRO") (pin "2") (pinfunction "2_2") (pintype "passive"))
    )
    (net (code "74") (name "HEATER_1_PWR") (class "Default")
      (node (ref "C3_CMD") (pin "8") (pinfunction "8_8") (pintype "passive"))
      (node (ref "H1") (pin "1") (pinfunction "S_1") (pintype "passive"))
      (node (ref "PO4") (pin "1") (pinfunction "P_1") (pintype "passive"))
    )
    (net (code "75") (name "HEATER_1_PWR_RTN") (class "Default")
      (node (ref "C3_CMD") (pin "9") (pinfunction "9_9") (pintype "passive"))
      (node (ref "H1") (pin "2") (pinfunction "S_2") (pintype "passive"))
      (node (ref "Q4") (pin "C") (pinfunction "C_C") (pintype "passive"))
    )
    (net (code "76") (name "HEATER_2_PWR") (class "Default")
      (node (ref "C3_CMD") (pin "10") (pinfunction "10_10") (pintype "passive"))
      (node (ref "H2") (pin "1") (pinfunction "S_1") (pintype "passive"))
      (node (ref "PO5") (pin "1") (pinfunction "P_1") (pintype "passive"))
    )
    (net (code "77") (name "HEATER_2_PWR_RTN") (class "Default")
      (node (ref "C3_CMD") (pin "11") (pinfunction "11_11") (pintype "passive"))
      (node (ref "H2") (pin "2") (pinfunction "S_2") (pintype "passive"))
      (node (ref "Q5") (pin "C") (pinfunction "C_C") (pintype "passive"))
    )
    (net (code "78") (name "HEATER_CONTROL_1") (class "Default")
      (node (ref "ARD_7") (pin "10") (pinfunction "10_10") (pintype "passive"))
      (node (ref "R10") (pin "2") (pinfunction "2_2") (pintype "passive"))
    )
    (net (code "79") (name "HEATER_CONTROL_2") (class "Default")
      (node (ref "ARD_6") (pin "3") (pinfunction "3_3") (pintype "passive"))
      (node (ref "R11") (pin "2") (pinfunction "2_2") (pintype "passive"))
    )
    (net (code "80") (name "IOREF") (class "Default")
      (node (ref "ARD_1") (pin "2") (pinfunction "2_2") (pintype "passive"))
    )
    (net (code "81") (name "LI_ION") (class "Default")
      (node (ref "RB2") (pin "7") (pinfunction "7_7") (pintype "passive"))
    )
    (net (code "82") (name "LOAD_IN") (class "Default")
      (node (ref "D1") (pin "C") (pinfunction "C_C") (pintype "passive"))
      (node (ref "D2") (pin "C") (pinfunction "C_C") (pintype "passive"))
      (node (ref "LCC") (pin "6") (pinfunction "6_6") (pintype "passive"))
    )
    (net (code "83") (name "MISO") (class "Default")
      (node (ref "ARD_4") (pin "1") (pinfunction "1_1") (pintype "passive"))
      (node (ref "ARD_7") (pin "6") (pinfunction "6_6") (pintype "passive"))
    )
    (net (code "84") (name "MOSI") (class "Default")
      (node (ref "ARD_4") (pin "4") (pinfunction "4_4") (pintype "passive"))
      (node (ref "ARD_7") (pin "7") (pinfunction "7_7") (pintype "passive"))
    )
    (net (code "85") (name "NET_AV") (class "Default")
      (node (ref "RB2") (pin "5") (pinfunction "5_5") (pintype "passive"))
    )
    (net (code "86") (name "Net-(B1C-S)") (class "Default")
      (node (ref "B1") (pin "3") (pinfunction "S_3") (pintype "passive"))
      (node (ref "B1_CELL_3") (pin "1") (pinfunction "P_1") (pintype "passive"))
    )
    (net (code "87") (name "Net-(B1D-S)") (class "Default")
      (node (ref "B1") (pin "4") (pinfunction "S_4") (pintype "passive"))
      (node (ref "B1_CELL_2") (pin "1") (pinfunction "P_1") (pintype "passive"))
    )
    (net (code "88") (name "Net-(B1E-S)") (class "Default")
      (node (ref "B1") (pin "5") (pinfunction "S_5") (pintype "passive"))
      (node (ref "B1_CELL_1") (pin "1") (pinfunction "P_1") (pintype "passive"))
    )
    (net (code "89") (name "Net-(B2C-S)") (class "Default")
      (node (ref "B2") (pin "3") (pinfunction "S_3") (pintype "passive"))
      (node (ref "B3_CELL_3") (pin "1") (pinfunction "P_1") (pintype "passive"))
    )
    (net (code "90") (name "Net-(B2D-S)") (class "Default")
      (node (ref "B2") (pin "4") (pinfunction "S_4") (pintype "passive"))
      (node (ref "B2_CELL_2") (pin "1") (pinfunction "P_1") (pintype "passive"))
    )
    (net (code "91") (name "Net-(B2E-S)") (class "Default")
      (node (ref "B2") (pin "5") (pinfunction "S_5") (pintype "passive"))
      (node (ref "B2_CELL_1") (pin "1") (pinfunction "P_1") (pintype "passive"))
    )
    (net (code "92") (name "Net-(Q4-PadB)") (class "Default")
      (node (ref "Q4") (pin "B") (pinfunction "B_B") (pintype "passive"))
      (node (ref "R10") (pin "1") (pinfunction "1_1") (pintype "passive"))
      (node (ref "R12") (pin "2") (pinfunction "2_2") (pintype "passive"))
    )
    (net (code "93") (name "Net-(Q5-PadB)") (class "Default")
      (node (ref "Q5") (pin "B") (pinfunction "B_B") (pintype "passive"))
      (node (ref "R11") (pin "1") (pinfunction "1_1") (pintype "passive"))
      (node (ref "R13") (pin "2") (pinfunction "2_2") (pintype "passive"))
    )
    (net (code "94") (name "Net-(Q6-PadB)") (class "Default")
      (node (ref "Q6") (pin "B") (pinfunction "B_B") (pintype "passive"))
      (node (ref "R16") (pin "1") (pinfunction "1_1") (pintype "passive"))
      (node (ref "R18") (pin "2") (pinfunction "2_2") (pintype "passive"))
    )
    (net (code "95") (name "Net-(Q7-PadB)") (class "Default")
      (node (ref "Q7") (pin "B") (pinfunction "B_B") (pintype "passive"))
      (node (ref "R17") (pin "1") (pinfunction "1_1") (pintype "passive"))
      (node (ref "R19") (pin "2") (pinfunction "2_2") (pintype "passive"))
    )
    (net (code "96") (name "Net-(T1-B)") (class "Default")
      (node (ref "R1") (pin "1") (pinfunction "1_1") (pintype "passive"))
      (node (ref "R2") (pin "2") (pinfunction "2_2") (pintype "passive"))
      (node (ref "T1") (pin "2") (pinfunction "B_2") (pintype "passive"))
    )
    (net (code "97") (name "Net-(T1-E)") (class "Default")
      (node (ref "Q1") (pin "B") (pinfunction "B_B") (pintype "passive"))
      (node (ref "R2") (pin "1") (pinfunction "1_1") (pintype "passive"))
      (node (ref "R3") (pin "2") (pinfunction "2_2") (pintype "passive"))
      (node (ref "T1") (pin "3") (pinfunction "E_3") (pintype "passive"))
    )
    (net (code "98") (name "Net-(T2-B)") (class "Default")
      (node (ref "R4") (pin "1") (pinfunction "1_1") (pintype "passive"))
      (node (ref "R6") (pin "2") (pinfunction "2_2") (pintype "passive"))
      (node (ref "T2") (pin "2") (pinfunction "B_2") (pintype "passive"))
    )
    (net (code "99") (name "Net-(T2-E)") (class "Default")
      (node (ref "Q2") (pin "B") (pinfunction "B_B") (pintype "passive"))
      (node (ref "R6") (pin "1") (pinfunction "1_1") (pintype "passive"))
      (node (ref "R8") (pin "2") (pinfunction "2_2") (pintype "passive"))
      (node (ref "T2") (pin "3") (pinfunction "E_3") (pintype "passive"))
    )
    (net (code "100") (name "Net-(T3-B)") (class "Default")
      (node (ref "R5") (pin "1") (pinfunction "1_1") (pintype "passive"))
      (node (ref "R7") (pin "2") (pinfunction "2_2") (pintype "passive"))
      (node (ref "T3") (pin "2") (pinfunction "B_2") (pintype "passive"))
    )
    (net (code "101") (name "Net-(T3-E)") (class "Default")
      (node (ref "Q3") (pin "B") (pinfunction "B_B") (pintype "passive"))
      (node (ref "R7") (pin "1") (pinfunction "1_1") (pintype "passive"))
      (node (ref "R9") (pin "2") (pinfunction "2_2") (pintype "passive"))
      (node (ref "T3") (pin "3") (pinfunction "E_3") (pintype "passive"))
    )
    (net (code "102") (name "ON_OFF") (class "Default")
      (node (ref "RB2") (pin "6") (pinfunction "6_6") (pintype "passive"))
    )
    (net (code "103") (name "PYRO_1_PWR") (class "Default")
      (node (ref "C3_CMD") (pin "1") (pinfunction "1_1") (pintype "passive"))
      (node (ref "PO1") (pin "1") (pinfunction "P_1") (pintype "passive"))
      (node (ref "PYRO1") (pin "1") (pinfunction "S_1") (pintype "passive"))
    )
    (net (code "104") (name "PYRO_1_PWR_RTN") (class "Default")
      (node (ref "C3_CMD") (pin "2") (pinfunction "2_2") (pintype "passive"))
      (node (ref "PYRO1") (pin "2") (pinfunction "S_2") (pintype "passive"))
      (node (ref "Q1") (pin "C") (pinfunction "C_C") (pintype "passive"))
      (node (ref "T1") (pin "1") (pinfunction "C_1") (pintype "passive"))
    )
    (net (code "105") (name "PYRO_2_PWR") (class "Default")
      (node (ref "C3_CMD") (pin "3") (pinfunction "3_3") (pintype "passive"))
      (node (ref "PO2") (pin "1") (pinfunction "P_1") (pintype "passive"))
      (node (ref "PYRO2") (pin "1") (pinfunction "S_1") (pintype "passive"))
    )
    (net (code "106") (name "PYRO_2_PWR_RTN") (class "Default")
      (node (ref "C3_CMD") (pin "4") (pinfunction "4_4") (pintype "passive"))
      (node (ref "PYRO2") (pin "2") (pinfunction "S_2") (pintype "passive"))
      (node (ref "Q2") (pin "C") (pinfunction "C_C") (pintype "passive"))
      (node (ref "T2") (pin "1") (pinfunction "C_1") (pintype "passive"))
    )
    (net (code "107") (name "RESET") (class "Default")
      (node (ref "ARD_1") (pin "3") (pinfunction "3_3") (pintype "passive"))
      (node (ref "ARD_4") (pin "5") (pinfunction "5_5") (pintype "passive"))
      (node (ref "ON/OFF") (pin "9") (pinfunction "S_9") (pintype "passive"))
    )
    (net (code "108") (name "RF_IN") (class "Default")
      (node (ref "GPS") (pin "2") (pinfunction "2_2") (pintype "passive"))
    )
    (net (code "109") (name "RI") (class "Default")
      (node (ref "RB2") (pin "4") (pinfunction "4_4") (pintype "passive"))
    )
    (net (code "110") (name "RTS") (class "Default")
      (node (ref "RB1") (pin "1") (pinfunction "1_1") (pintype "passive"))
    )
    (net (code "111") (name "RX0") (class "Default")
      (node (ref "ARD_6") (pin "8") (pinfunction "8_8") (pintype "passive"))
      (node (ref "X12") (pin "2") (pinfunction "D-_2") (pintype "bidirectional"))
    )
    (net (code "112") (name "RX1") (class "Default")
      (node (ref "ARD_5") (pin "6") (pinfunction "6_6") (pintype "passive"))
      (node (ref "GPS") (pin "5") (pinfunction "5_5") (pintype "passive"))
    )
    (net (code "113") (name "RX2") (class "Default")
      (node (ref "ARD_5") (pin "4") (pinfunction "4_4") (pintype "passive"))
    )
    (net (code "114") (name "RX3") (class "Default")
      (node (ref "ARD_5") (pin "2") (pinfunction "2_2") (pintype "passive"))
      (node (ref "RB1") (pin "2") (pinfunction "2_2") (pintype "passive"))
    )
    (net (code "115") (name "RXB") (class "Default")
      (node (ref "GPS") (pin "7") (pinfunction "7_7") (pintype "passive"))
    )
    (net (code "116") (name "SCK") (class "Default")
      (node (ref "ARD_4") (pin "3") (pinfunction "3_3") (pintype "passive"))
      (node (ref "ARD_7") (pin "5") (pinfunction "5_5") (pintype "passive"))
    )
    (net (code "117") (name "SCL") (class "Default")
      (node (ref "ARD_5") (pin "8") (pinfunction "8_8") (pintype "passive"))
      (node (ref "B1CC") (pin "3") (pinfunction "3_3") (pintype "passive"))
      (node (ref "B2CC") (pin "3") (pinfunction "3_3") (pintype "passive"))
      (node (ref "GYRO") (pin "4") (pinfunction "4_4") (pintype "passive"))
      (node (ref "LCC") (pin "3") (pinfunction "3_3") (pintype "passive"))
      (node (ref "SACC") (pin "3") (pinfunction "3_3") (pintype "passive"))
    )
    (net (code "118") (name "SCL1") (class "Default")
      (node (ref "ARD_7") (pin "1") (pinfunction "1_1") (pintype "passive"))
    )
    (net (code "119") (name "SDA") (class "Default")
      (node (ref "ARD_5") (pin "7") (pinfunction "7_7") (pintype "passive"))
      (node (ref "B1CC") (pin "4") (pinfunction "4_4") (pintype "passive"))
      (node (ref "B2CC") (pin "4") (pinfunction "4_4") (pintype "passive"))
      (node (ref "GYRO") (pin "3") (pinfunction "3_3") (pintype "passive"))
      (node (ref "LCC") (pin "4") (pinfunction "4_4") (pintype "passive"))
      (node (ref "SACC") (pin "4") (pinfunction "4_4") (pintype "passive"))
    )
    (net (code "120") (name "SDA1") (class "Default")
      (node (ref "ARD_7") (pin "2") (pinfunction "2_2") (pintype "passive"))
    )
    (net (code "121") (name "SPARE_1_PWR") (class "Default")
      (node (ref "C3_CMD") (pin "12") (pinfunction "12_12") (pintype "passive"))
      (node (ref "PO6") (pin "1") (pinfunction "P_1") (pintype "passive"))
      (node (ref "SPRL1") (pin "1") (pinfunction "S_1") (pintype "passive"))
    )
    (net (code "122") (name "SPARE_1_PWR_RTN") (class "Default")
      (node (ref "C3_CMD") (pin "13") (pinfunction "13_13") (pintype "passive"))
      (node (ref "Q6") (pin "C") (pinfunction "C_C") (pintype "passive"))
      (node (ref "SPRL1") (pin "2") (pinfunction "S_2") (pintype "passive"))
    )
    (net (code "123") (name "SPARE_2_PWR") (class "Default")
      (node (ref "C3_CMD") (pin "14") (pinfunction "14_14") (pintype "passive"))
      (node (ref "PO7") (pin "1") (pinfunction "P_1") (pintype "passive"))
      (node (ref "SPRL2") (pin "1") (pinfunction "S_1") (pintype "passive"))
    )
    (net (code "124") (name "SPARE_2_PWR_RTN") (class "Default")
      (node (ref "C3_CMD") (pin "15") (pinfunction "15_15") (pintype "passive"))
      (node (ref "Q7") (pin "C") (pinfunction "C_C") (pintype "passive"))
      (node (ref "SPRL2") (pin "2") (pinfunction "S_2") (pintype "passive"))
    )
    (net (code "125") (name "SPARE_HIGH_1_CONTROL") (class "Default")
      (node (ref "ARD_9") (pin "2") (pinfunction "2_2") (pintype "passive"))
      (node (ref "R5") (pin "2") (pinfunction "2_2") (pintype "passive"))
    )
    (net (code "126") (name "SPARE_HIGH_1_PWR") (class "Default")
      (node (ref "C3_CMD") (pin "5") (pinfunction "5_5") (pintype "passive"))
      (node (ref "PO3") (pin "1") (pinfunction "P_1") (pintype "passive"))
      (node (ref "SPRH1") (pin "1") (pinfunction "S_1") (pintype "passive"))
    )
    (net (code "127") (name "SPARE_HIGH_1_PWR_RTN") (class "Default")
      (node (ref "C3_CMD") (pin "6") (pinfunction "6_6") (pintype "passive"))
      (node (ref "Q3") (pin "C") (pinfunction "C_C") (pintype "passive"))
      (node (ref "SPRH1") (pin "2") (pinfunction "S_2") (pintype "passive"))
      (node (ref "T3") (pin "1") (pinfunction "C_1") (pintype "passive"))
    )
    (net (code "128") (name "SPARE_LOW_1_CONTROL") (class "Default")
      (node (ref "ARD_9") (pin "3") (pinfunction "3_3") (pintype "passive"))
      (node (ref "R16") (pin "2") (pinfunction "2_2") (pintype "passive"))
    )
    (net (code "129") (name "SPARE_LOW_2_CONTROL") (class "Default")
      (node (ref "ARD_9") (pin "4") (pinfunction "4_4") (pintype "passive"))
      (node (ref "R17") (pin "2") (pinfunction "2_2") (pintype "passive"))
    )
    (net (code "130") (name "S{slash}A_PWR_IN") (class "Default")
      (node (ref "C2_PWR") (pin "10") (pinfunction "10_10") (pintype "passive"))
      (node (ref "C2_PWR") (pin "6") (pinfunction "6_6") (pintype "passive"))
      (node (ref "C2_PWR") (pin "8") (pinfunction "8_8") (pintype "passive"))
      (node (ref "SACC") (pin "6") (pinfunction "6_6") (pintype "passive"))
    )
    (net (code "131") (name "S{slash}A_PWR_OUT") (class "Default")
      (node (ref "MPPT") (pin "3") (pinfunction "S_3") (pintype "passive"))
      (node (ref "SACC") (pin "5") (pinfunction "5_5") (pintype "passive"))
    )
    (net (code "132") (name "S{slash}A_PWR_RTN") (class "Default")
      (node (ref "C2_PWR") (pin "11") (pinfunction "11_11") (pintype "passive"))
      (node (ref "C2_PWR") (pin "7") (pinfunction "7_7") (pintype "passive"))
      (node (ref "C2_PWR") (pin "9") (pinfunction "9_9") (pintype "passive"))
      (node (ref "MPPT") (pin "4") (pinfunction "S_4") (pintype "passive"))
    )
    (net (code "133") (name "TEMP_EXT_1") (class "Default")
      (node (ref "ARD_2") (pin "8") (pinfunction "8_8") (pintype "passive"))
      (node (ref "C1_TLM") (pin "1") (pinfunction "1_1") (pintype "passive"))
      (node (ref "R22") (pin "1") (pinfunction "1_1") (pintype "passive"))
      (node (ref "R23") (pin "2") (pinfunction "2_2") (pintype "passive"))
    )
    (net (code "134") (name "TEMP_EXT_2") (class "Default")
      (node (ref "ARD_2") (pin "6") (pinfunction "6_6") (pintype "passive"))
      (node (ref "C1_TLM") (pin "3") (pinfunction "3_3") (pintype "passive"))
      (node (ref "R24") (pin "1") (pinfunction "1_1") (pintype "passive"))
      (node (ref "R25") (pin "2") (pinfunction "2_2") (pintype "passive"))
    )
    (net (code "135") (name "TX0") (class "Default")
      (node (ref "ARD_6") (pin "7") (pinfunction "7_7") (pintype "passive"))
      (node (ref "X12") (pin "3") (pinfunction "D+_3") (pintype "bidirectional"))
    )
    (net (code "136") (name "TX1") (class "Default")
      (node (ref "ARD_5") (pin "5") (pinfunction "5_5") (pintype "passive"))
      (node (ref "GPS") (pin "4") (pinfunction "4_4") (pintype "passive"))
    )
    (net (code "137") (name "TX2") (class "Default")
      (node (ref "ARD_5") (pin "3") (pinfunction "3_3") (pintype "passive"))
    )
    (net (code "138") (name "TX3") (class "Default")
      (node (ref "ARD_5") (pin "1") (pinfunction "1_1") (pintype "passive"))
      (node (ref "RB1") (pin "3") (pinfunction "3_3") (pintype "passive"))
    )
    (net (code "139") (name "TXB") (class "Default")
      (node (ref "GPS") (pin "6") (pinfunction "6_6") (pintype "passive"))
    )
    (net (code "140") (name "UNKNOWN") (class "Default")
      (node (ref "ARD_1") (pin "1") (pinfunction "1_1") (pintype "passive"))
    )
    (net (code "141") (name "VBAT") (class "Default")
      (node (ref "GPS") (pin "3") (pinfunction "3_3") (pintype "passive"))
    )
    (net (code "142") (name "VCC_RB") (class "Default")
      (node (ref "RB1") (pin "4") (pinfunction "4_4") (pintype "passive"))
    )
    (net (code "143") (name "VIN") (class "Default")
      (node (ref "ARD_1") (pin "8") (pinfunction "8_8") (pintype "passive"))
      (node (ref "LCC") (pin "5") (pinfunction "5_5") (pintype "passive"))
      (node (ref "PVIN1") (pin "1") (pinfunction "P_1") (pintype "passive"))
      (node (ref "PVIN2") (pin "1") (pinfunction "P_1") (pintype "passive"))
      (node (ref "PVIN3") (pin "1") (pinfunction "P_1") (pintype "passive"))
      (node (ref "PVIN4") (pin "1") (pinfunction "P_1") (pintype "passive"))
      (node (ref "PVIN5") (pin "1") (pinfunction "P_1") (pintype "passive"))
      (node (ref "PVIN6") (pin "1") (pinfunction "P_1") (pintype "passive"))
      (node (ref "PVIN7") (pin "1") (pinfunction "P_1") (pintype "passive"))
      (node (ref "R14") (pin "2") (pinfunction "2_2") (pintype "passive"))
    )
    (net (code "144") (name "VIN_VOLTAGE_TLM") (class "Default")
      (node (ref "ARD_2") (pin "4") (pinfunction "4_4") (pintype "passive"))
      (node (ref "C1") (pin "1") (pinfunction "1_1") (pintype "passive"))
      (node (ref "R14") (pin "1") (pinfunction "1_1") (pintype "passive"))
      (node (ref "R15") (pin "2") (pinfunction "2_2") (pintype "passive"))
    )
    (net (code "145") (name "unconnected-(ALT-Pad8)") (class "Default")
      (node (ref "ALT") (pin "8") (pinfunction "8_8") (pintype "passive"))
    )
    (net (code "146") (name "unconnected-(B1B-S-Pad2)") (class "Default")
      (node (ref "B1") (pin "2") (pinfunction "S_2") (pintype "passive"))
    )
    (net (code "147") (name "unconnected-(B2B-S-Pad2)") (class "Default")
      (node (ref "B2") (pin "2") (pinfunction "S_2") (pintype "passive"))
    )
    (net (code "148") (name "unconnected-(C1_TLM-Pad5)") (class "Default")
      (node (ref "C1_TLM") (pin "5") (pinfunction "5_5") (pintype "passive"))
    )
    (net (code "149") (name "unconnected-(C1_TLM-Pad6)") (class "Default")
      (node (ref "C1_TLM") (pin "6") (pinfunction "6_6") (pintype "passive"))
    )
    (net (code "150") (name "unconnected-(C1_TLM-Pad7)") (class "Default")
      (node (ref "C1_TLM") (pin "7") (pinfunction "7_7") (pintype "passive"))
    )
    (net (code "151") (name "unconnected-(C1_TLM-Pad8)") (class "Default")
      (node (ref "C1_TLM") (pin "8") (pinfunction "8_8") (pintype "passive"))
    )
    (net (code "152") (name "unconnected-(C1_TLM-Pad9)") (class "Default")
      (node (ref "C1_TLM") (pin "9") (pinfunction "9_9") (pintype "passive"))
    )
    (net (code "153") (name "unconnected-(C1_TLM-Pad10)") (class "Default")
      (node (ref "C1_TLM") (pin "10") (pinfunction "10_10") (pintype "passive"))
    )
    (net (code "154") (name "unconnected-(C1_TLM-Pad11)") (class "Default")
      (node (ref "C1_TLM") (pin "11") (pinfunction "11_11") (pintype "passive"))
    )
    (net (code "155") (name "unconnected-(C1_TLM-Pad12)") (class "Default")
      (node (ref "C1_TLM") (pin "12") (pinfunction "12_12") (pintype "passive"))
    )
    (net (code "156") (name "unconnected-(C1_TLM-Pad13)") (class "Default")
      (node (ref "C1_TLM") (pin "13") (pinfunction "13_13") (pintype "passive"))
    )
    (net (code "157") (name "unconnected-(C1_TLM-Pad14)") (class "Default")
      (node (ref "C1_TLM") (pin "14") (pinfunction "14_14") (pintype "passive"))
    )
    (net (code "158") (name "unconnected-(C1_TLM-Pad15)") (class "Default")
      (node (ref "C1_TLM") (pin "15") (pinfunction "15_15") (pintype "passive"))
    )
    (net (code "159") (name "unconnected-(C2_PWR-Pad5)") (class "Default")
      (node (ref "C2_PWR") (pin "5") (pinfunction "5_5") (pintype "passive"))
    )
    (net (code "160") (name "unconnected-(C2_PWR-Pad12)") (class "Default")
      (node (ref "C2_PWR") (pin "12") (pinfunction "12_12") (pintype "passive"))
    )
    (net (code "161") (name "unconnected-(C2_PWR-Pad13)") (class "Default")
      (node (ref "C2_PWR") (pin "13") (pinfunction "13_13") (pintype "passive"))
    )
    (net (code "162") (name "unconnected-(C2_PWR-Pad14)") (class "Default")
      (node (ref "C2_PWR") (pin "14") (pinfunction "14_14") (pintype "passive"))
    )
    (net (code "163") (name "unconnected-(C2_PWR-Pad15)") (class "Default")
      (node (ref "C2_PWR") (pin "15") (pinfunction "15_15") (pintype "passive"))
    )
    (net (code "164") (name "unconnected-(C3_CMD-Pad7)") (class "Default")
      (node (ref "C3_CMD") (pin "7") (pinfunction "7_7") (pintype "passive"))
    )
  )
)
